# 433Mhz_Remote_Receiver.net
KiCad netlist of a schematic drawn in Altium Designer
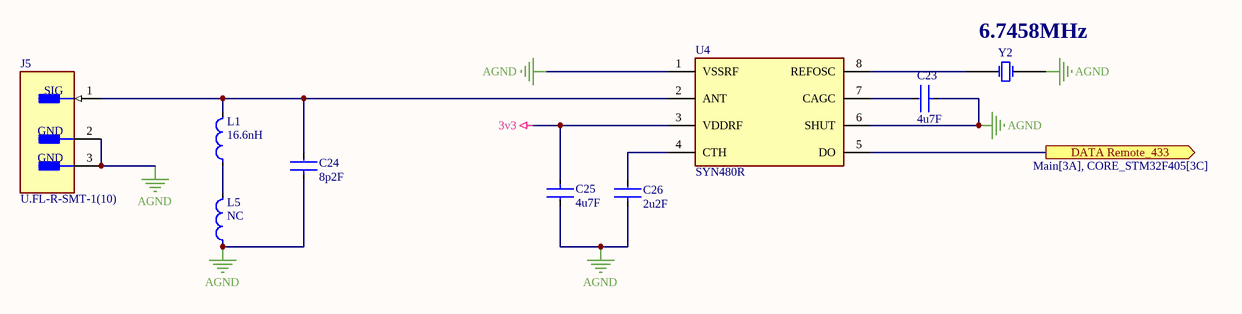
[diagram p0: 433Mhz Remote Receiver.SchDoc]

(export (version "E")
  (design (tool "Eeschema 10.0.6"))
  (components
    (comp (ref "C23")
      (value "4u7F")
      (footprint "Hosein_PCB_Lib_SMD:CAP-0603")
      (description "Chip Multilayer Ceramic Capacitors for General Purpose, 0603")
      (fields (field (name "VOLTAGE") "6.3V") (field (name "TOLERANCE") "20%"))
      (libsource (lib "Hosein_PCB_Lib") (part "CAP-Ceramic"))
    )
    (comp (ref "C24")
      (value "8p2F")
      (footprint "Hosein_PCB_Lib_SMD:CAP-0603")
      (description "Chip Multilayer Ceramic Capacitors for General Purpose, 0603")
      (fields (field (name "VOLTAGE") "6.3V") (field (name "TOLERANCE") "20%"))
      (libsource (lib "Hosein_PCB_Lib") (part "CAP-Ceramic"))
    )
    (comp (ref "C25")
      (value "4u7F")
      (footprint "Hosein_PCB_Lib_SMD:CAP-0603")
      (description "Chip Multilayer Ceramic Capacitors for General Purpose, 0603")
      (fields (field (name "VOLTAGE") "6.3V") (field (name "TOLERANCE") "20%"))
      (libsource (lib "Hosein_PCB_Lib") (part "CAP-Ceramic"))
    )
    (comp (ref "C26")
      (value "2u2F")
      (footprint "Hosein_PCB_Lib_SMD:CAP-0603")
      (description "Chip Multilayer Ceramic Capacitors for General Purpose, 0603")
      (fields (field (name "VOLTAGE") "6.3V") (field (name "TOLERANCE") "20%"))
      (libsource (lib "Hosein_PCB_Lib") (part "CAP-Ceramic"))
    )
    (comp (ref "J5")
      (value "U.FL-R-SMT-1(10)")
      (footprint "Hirose U.FL_SMT-1_10-MFG")
      (description "CONN U.FL RCPT STR 50 OHM SMD\r\nRF connector for high-frequency signals up to 6 GHz")
      (libsource (lib "Connectors Header") (part "Hirose U.FL"))
    )
    (comp (ref "L1")
      (value "16.6nH")
      (footprint "ind-0603-MFG")
      (description "Inductor")
      (libsource (lib "Hosein_PCB_Lib") (part "inductor"))
    )
    (comp (ref "L5")
      (value "NC")
      (footprint "ind-0603-MFG")
      (description "Inductor")
      (libsource (lib "Hosein_PCB_Lib") (part "inductor"))
    )
    (comp (ref "U4")
      (value "SYN480R")
      (footprint "SOP8")
      (description "single chip ASK/OOK (ON-OFF Keyed) RF receiver IC. 300MHz to 450MHz frequency range")
      (libsource (lib "Module & IC") (part "SYN480R"))
    )
    (comp (ref "Y2")
      (value "6.7458MHz")
      (footprint "CRYSTAL Small")
      (description "XTAL Crystal")
      (fields (field (name "DESIGNER") "ABBAS BASEREH"))
      (libsource (lib "General 1") (part "XTAL_Crystal"))
    )
  )
  (nets
    (net (code "1") (name "/DATA Remote_433") (class "Default")
      (node (ref "U4") (pin "5") (pinfunction "DO_5") (pintype "open_collector"))
    )
    (net (code "2") (name "3v3") (class "Default")
      (node (ref "C25") (pin "1") (pinfunction "1_1") (pintype "passive"))
      (node (ref "U4") (pin "3") (pinfunction "VDDRF_3") (pintype "power_in"))
    )
    (net (code "3") (name "AGND") (class "Default")
      (node (ref "C23") (pin "1") (pinfunction "1_1") (pintype "passive"))
      (node (ref "C24") (pin "1") (pinfunction "1_1") (pintype "passive"))
      (node (ref "C25") (pin "2") (pinfunction "2_2") (pintype "passive"))
      (node (ref "C26") (pin "1") (pinfunction "1_1") (pintype "passive"))
      (node (ref "J5") (pin "2") (pinfunction "GND_2") (pintype "power_in"))
      (node (ref "J5") (pin "3") (pinfunction "GND_3") (pintype "power_in"))
      (node (ref "L5") (pin "1") (pinfunction "1_1") (pintype "passive"))
      (node (ref "U4") (pin "1") (pinfunction "VSSRF_1") (pintype "passive"))
      (node (ref "U4") (pin "6") (pinfunction "SHUT_6") (pintype "power_in"))
      (node (ref "Y2") (pin "2") (pinfunction "OSC2_2") (pintype "passive"))
    )
    (net (code "4") (name "Net-(J5-SIG)") (class "Default")
      (node (ref "C24") (pin "2") (pinfunction "2_2") (pintype "passive"))
      (node (ref "J5") (pin "1") (pinfunction "SIG_1") (pintype "input"))
      (node (ref "L1") (pin "2") (pinfunction "2_2") (pintype "passive"))
      (node (ref "U4") (pin "2") (pinfunction "ANT_2") (pintype "power_in"))
    )
    (net (code "5") (name "Net-(L1-Pad1)") (class "Default")
      (node (ref "L1") (pin "1") (pinfunction "1_1") (pintype "passive"))
      (node (ref "L5") (pin "2") (pinfunction "2_2") (pintype "passive"))
    )
    (net (code "6") (name "Net-(U4-CAGC)") (class "Default")
      (node (ref "C23") (pin "2") (pinfunction "2_2") (pintype "passive"))
      (node (ref "U4") (pin "7") (pinfunction "CAGC_7") (pintype "passive"))
    )
    (net (code "7") (name "Net-(U4-CTH)") (class "Default")
      (node (ref "C26") (pin "2") (pinfunction "2_2") (pintype "passive"))
      (node (ref "U4") (pin "4") (pinfunction "CTH_4") (pintype "open_collector"))
    )
    (net (code "8") (name "Net-(U4-REFOSC)") (class "Default")
      (node (ref "U4") (pin "8") (pinfunction "REFOSC_8") (pintype "power_in"))
      (node (ref "Y2") (pin "1") (pinfunction "OSC1_1") (pintype "passive"))
    )
  )
)
